# mMWCv0_2.net
KiCad netlist of a schematic drawn in EAGLE
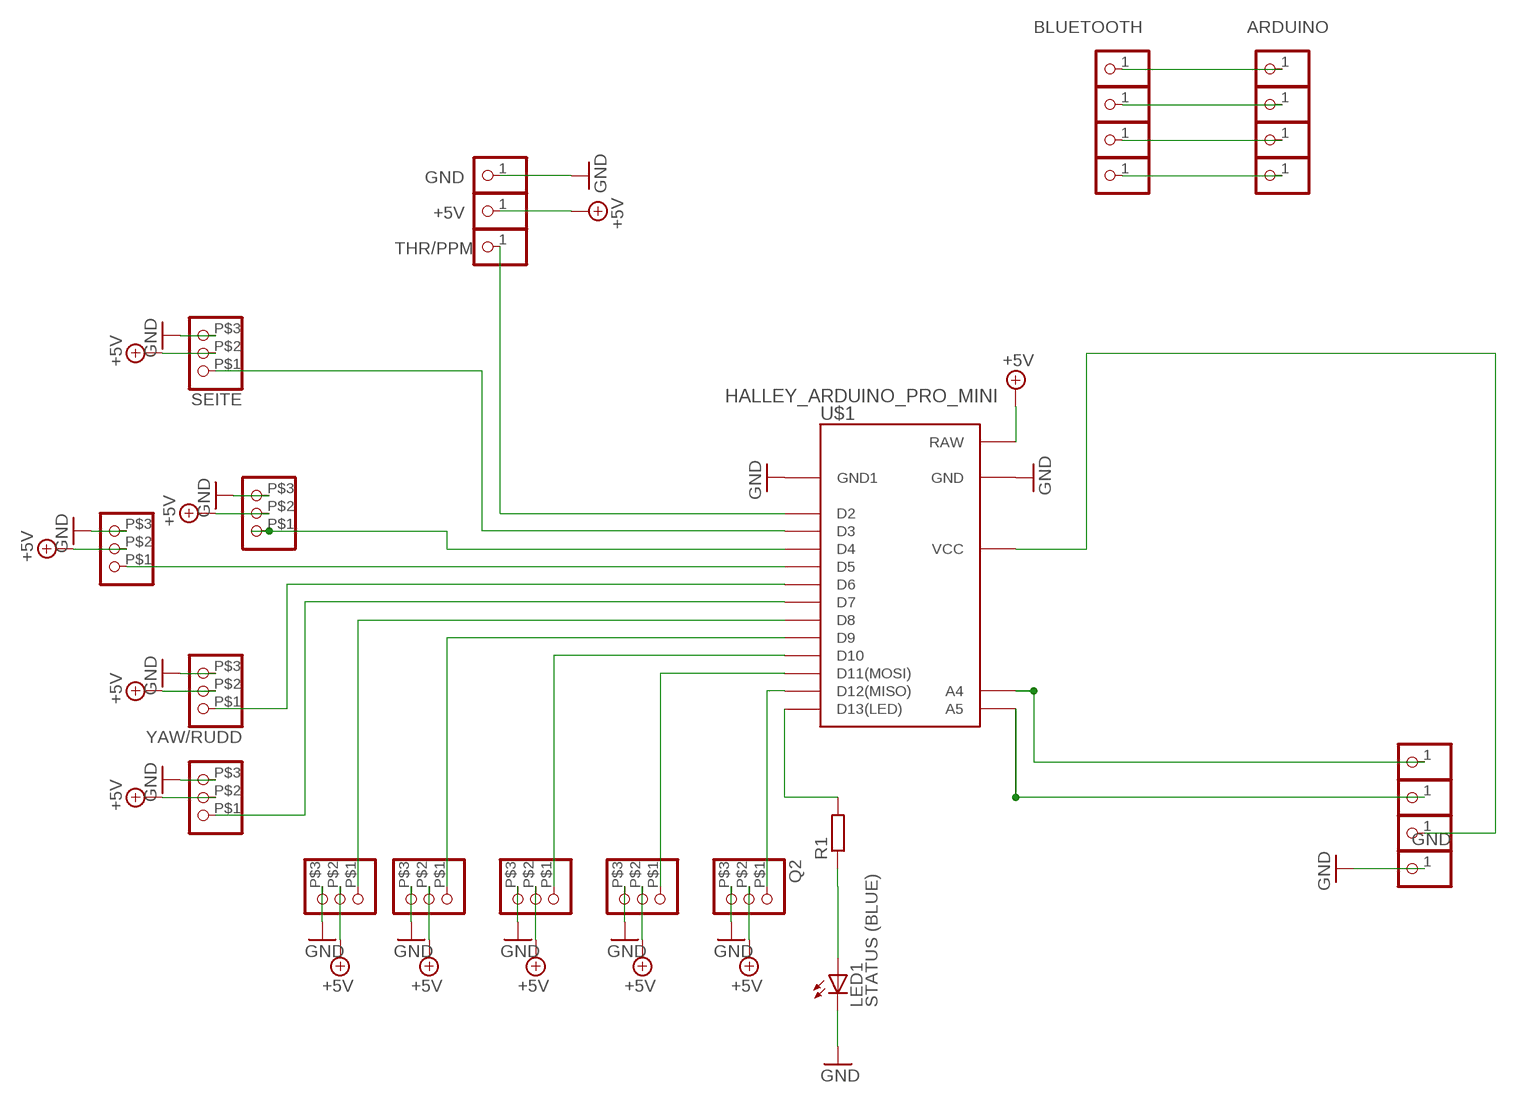
[diagram p0: schematic, sheet 1]

(export (version "E")
  (design (tool "Eeschema 10.0.6"))
  (components
    (comp (ref "+5V")
      (value "PINHD-1X1")
      (footprint "eagle-import:1X01")
      (libsource (lib "eagle-import") (part "PINHD-1X1"))
    )
    (comp (ref "5V")
      (value "PINHD-1X1")
      (footprint "eagle-import:1X01")
      (libsource (lib "eagle-import") (part "PINHD-1X1"))
    )
    (comp (ref "A4")
      (value "PINHD-1X1")
      (footprint "eagle-import:1X01")
      (libsource (lib "eagle-import") (part "PINHD-1X1"))
    )
    (comp (ref "A5")
      (value "PINHD-1X1")
      (footprint "eagle-import:1X01")
      (libsource (lib "eagle-import") (part "PINHD-1X1"))
    )
    (comp (ref "AIL")
      (value "PINHEAD_PINHD-1X3")
      (footprint "eagle-import:PINHEAD_1X03")
      (libsource (lib "eagle-import") (part "PINHEAD_PINHD-1X3"))
    )
    (comp (ref "ARD_GND")
      (value "PINHD-1X1")
      (footprint "eagle-import:1X01")
      (libsource (lib "eagle-import") (part "PINHD-1X1"))
    )
    (comp (ref "ARD_RX")
      (value "PINHD-1X1")
      (footprint "eagle-import:1X01")
      (libsource (lib "eagle-import") (part "PINHD-1X1"))
    )
    (comp (ref "ARD_TX")
      (value "PINHD-1X1")
      (footprint "eagle-import:1X01")
      (libsource (lib "eagle-import") (part "PINHD-1X1"))
    )
    (comp (ref "ARD_VCC")
      (value "GND")
      (footprint "eagle-import:1X01")
      (libsource (lib "eagle-import") (part "PINHD-1X1"))
    )
    (comp (ref "AUX2")
      (value "PINHEAD_PINHD-1X3")
      (footprint "eagle-import:PINHEAD_1X03")
      (libsource (lib "eagle-import") (part "PINHEAD_PINHD-1X3"))
    )
    (comp (ref "BT_GND")
      (value "PINHD-1X1")
      (footprint "eagle-import:1X01")
      (libsource (lib "eagle-import") (part "PINHD-1X1"))
    )
    (comp (ref "BT_RX")
      (value "PINHD-1X1")
      (footprint "eagle-import:1X01")
      (libsource (lib "eagle-import") (part "PINHD-1X1"))
    )
    (comp (ref "BT_TX")
      (value "PINHD-1X1")
      (footprint "eagle-import:1X01")
      (libsource (lib "eagle-import") (part "PINHD-1X1"))
    )
    (comp (ref "BT_VCC")
      (value "GND")
      (footprint "eagle-import:1X01")
      (libsource (lib "eagle-import") (part "PINHD-1X1"))
    )
    (comp (ref "ELE/PITCH")
      (value "PINHEAD_PINHD-1X3")
      (footprint "eagle-import:PINHEAD_1X03")
      (libsource (lib "eagle-import") (part "PINHEAD_PINHD-1X3"))
    )
    (comp (ref "GND")
      (value "PINHD-1X1")
      (footprint "eagle-import:1X01")
      (libsource (lib "eagle-import") (part "PINHD-1X1"))
    )
    (comp (ref "GND_")
      (value "GND")
      (footprint "eagle-import:1X01")
      (libsource (lib "eagle-import") (part "PINHD-1X1"))
    )
    (comp (ref "HÖHE")
      (value "PINHEAD_PINHD-1X3")
      (footprint "eagle-import:PINHEAD_1X03")
      (libsource (lib "eagle-import") (part "PINHEAD_PINHD-1X3"))
    )
    (comp (ref "LED1")
      (value "STATUS (BLUE)")
      (footprint "eagle-import:CHIPLED_1206")
      (libsource (lib "eagle-import") (part "LEDCHIPLED_1206"))
    )
    (comp (ref "MODE")
      (value "PINHEAD_PINHD-1X3")
      (footprint "eagle-import:PINHEAD_1X03")
      (libsource (lib "eagle-import") (part "PINHEAD_PINHD-1X3"))
    )
    (comp (ref "MOTOR")
      (value "PINHEAD_PINHD-1X3")
      (footprint "eagle-import:PINHEAD_1X03")
      (libsource (lib "eagle-import") (part "PINHEAD_PINHD-1X3"))
    )
    (comp (ref "Q1")
      (value "PINHEAD_PINHD-1X3")
      (footprint "eagle-import:PINHEAD_1X03")
      (libsource (lib "eagle-import") (part "PINHEAD_PINHD-1X3"))
    )
    (comp (ref "Q2")
      (value "PINHEAD_PINHD-1X3")
      (footprint "eagle-import:PINHEAD_1X03")
      (libsource (lib "eagle-import") (part "PINHEAD_PINHD-1X3"))
    )
    (comp (ref "R1")
      (value "R-EU_R1206")
      (footprint "eagle-import:R1206")
      (libsource (lib "eagle-import") (part "R-EU_R1206"))
    )
    (comp (ref "SEITE")
      (value "PINHEAD_PINHD-1X3")
      (footprint "eagle-import:PINHEAD_1X03")
      (libsource (lib "eagle-import") (part "PINHEAD_PINHD-1X3"))
    )
    (comp (ref "THR/PPM")
      (value "PINHD-1X1")
      (footprint "eagle-import:1X01")
      (libsource (lib "eagle-import") (part "PINHD-1X1"))
    )
    (comp (ref "U$1")
      (value "HALLEY_ARDUINO_PRO_MINI")
      (footprint "eagle-import:HALLEY_ARDUINO_PRO_MINI")
      (libsource (lib "eagle-import") (part "HALLEY_ARDUINO_PRO_MINI"))
    )
    (comp (ref "YAW/RUDD")
      (value "PINHEAD_PINHD-1X3")
      (footprint "eagle-import:PINHEAD_1X03")
      (libsource (lib "eagle-import") (part "PINHEAD_PINHD-1X3"))
    )
  )
  (nets
    (net (code "1") (name "+5V") (class "Default")
      (node (ref "+5V") (pin "1") (pinfunction "1_1") (pintype "passive"))
      (node (ref "AIL") (pin "P$2") (pinfunction "2_P$2") (pintype "passive"))
      (node (ref "AUX2") (pin "P$2") (pinfunction "2_P$2") (pintype "passive"))
      (node (ref "ELE/PITCH") (pin "P$2") (pinfunction "2_P$2") (pintype "passive"))
      (node (ref "HÖHE") (pin "P$2") (pinfunction "2_P$2") (pintype "passive"))
      (node (ref "MODE") (pin "P$2") (pinfunction "2_P$2") (pintype "passive"))
      (node (ref "MOTOR") (pin "P$2") (pinfunction "2_P$2") (pintype "passive"))
      (node (ref "Q1") (pin "P$2") (pinfunction "2_P$2") (pintype "passive"))
      (node (ref "Q2") (pin "P$2") (pinfunction "2_P$2") (pintype "passive"))
      (node (ref "SEITE") (pin "P$2") (pinfunction "2_P$2") (pintype "passive"))
      (node (ref "U$1") (pin "RAW") (pinfunction "RAW_RAW") (pintype "bidirectional"))
      (node (ref "YAW/RUDD") (pin "P$2") (pinfunction "2_P$2") (pintype "passive"))
    )
    (net (code "2") (name "GND") (class "Default")
      (node (ref "AIL") (pin "P$3") (pinfunction "3_P$3") (pintype "passive"))
      (node (ref "AUX2") (pin "P$3") (pinfunction "3_P$3") (pintype "passive"))
      (node (ref "ELE/PITCH") (pin "P$3") (pinfunction "3_P$3") (pintype "passive"))
      (node (ref "GND") (pin "1") (pinfunction "1_1") (pintype "passive"))
      (node (ref "GND_") (pin "1") (pinfunction "1_1") (pintype "passive"))
      (node (ref "HÖHE") (pin "P$3") (pinfunction "3_P$3") (pintype "passive"))
      (node (ref "LED1") (pin "C") (pinfunction "C_C") (pintype "passive"))
      (node (ref "MODE") (pin "P$3") (pinfunction "3_P$3") (pintype "passive"))
      (node (ref "MOTOR") (pin "P$3") (pinfunction "3_P$3") (pintype "passive"))
      (node (ref "Q1") (pin "P$3") (pinfunction "3_P$3") (pintype "passive"))
      (node (ref "Q2") (pin "P$3") (pinfunction "3_P$3") (pintype "passive"))
      (node (ref "SEITE") (pin "P$3") (pinfunction "3_P$3") (pintype "passive"))
      (node (ref "U$1") (pin "GND") (pinfunction "GND1_GND") (pintype "bidirectional"))
      (node (ref "U$1") (pin "GND1") (pinfunction "GND_GND1") (pintype "bidirectional"))
      (node (ref "YAW/RUDD") (pin "P$3") (pinfunction "3_P$3") (pintype "passive"))
    )
    (net (code "3") (name "Net-(5V-Pad1)") (class "Default")
      (node (ref "5V") (pin "1") (pinfunction "1_1") (pintype "passive"))
      (node (ref "U$1") (pin "VCC") (pinfunction "VCC_VCC") (pintype "bidirectional"))
    )
    (net (code "4") (name "Net-(A4-Pad1)") (class "Default")
      (node (ref "A4") (pin "1") (pinfunction "1_1") (pintype "passive"))
      (node (ref "U$1") (pin "A4") (pinfunction "A4_A4") (pintype "bidirectional"))
    )
    (net (code "5") (name "Net-(A5-Pad1)") (class "Default")
      (node (ref "A5") (pin "1") (pinfunction "1_1") (pintype "passive"))
      (node (ref "U$1") (pin "A5") (pinfunction "A5_A5") (pintype "bidirectional"))
    )
    (net (code "6") (name "Net-(AIL-1)") (class "Default")
      (node (ref "AIL") (pin "P$1") (pinfunction "1_P$1") (pintype "passive"))
      (node (ref "U$1") (pin "D4") (pinfunction "D4_D4") (pintype "bidirectional"))
    )
    (net (code "7") (name "Net-(ARD_GND-Pad1)") (class "Default")
      (node (ref "ARD_GND") (pin "1") (pinfunction "1_1") (pintype "passive"))
      (node (ref "BT_GND") (pin "1") (pinfunction "1_1") (pintype "passive"))
    )
    (net (code "8") (name "Net-(ARD_RX-Pad1)") (class "Default")
      (node (ref "ARD_RX") (pin "1") (pinfunction "1_1") (pintype "passive"))
      (node (ref "BT_TX") (pin "1") (pinfunction "1_1") (pintype "passive"))
    )
    (net (code "9") (name "Net-(ARD_TX-Pad1)") (class "Default")
      (node (ref "ARD_TX") (pin "1") (pinfunction "1_1") (pintype "passive"))
      (node (ref "BT_RX") (pin "1") (pinfunction "1_1") (pintype "passive"))
    )
    (net (code "10") (name "Net-(ARD_VCC-Pad1)") (class "Default")
      (node (ref "ARD_VCC") (pin "1") (pinfunction "1_1") (pintype "passive"))
      (node (ref "BT_VCC") (pin "1") (pinfunction "1_1") (pintype "passive"))
    )
    (net (code "11") (name "Net-(AUX2-1)") (class "Default")
      (node (ref "AUX2") (pin "P$1") (pinfunction "1_P$1") (pintype "passive"))
      (node (ref "U$1") (pin "D8") (pinfunction "D8_D8") (pintype "bidirectional"))
    )
    (net (code "12") (name "Net-(ELE/PITCH-1)") (class "Default")
      (node (ref "ELE/PITCH") (pin "P$1") (pinfunction "1_P$1") (pintype "passive"))
      (node (ref "U$1") (pin "D5") (pinfunction "D5_D5") (pintype "bidirectional"))
    )
    (net (code "13") (name "Net-(HÖHE-1)") (class "Default")
      (node (ref "HÖHE") (pin "P$1") (pinfunction "1_P$1") (pintype "passive"))
      (node (ref "U$1") (pin "D10") (pinfunction "D10_D10") (pintype "bidirectional"))
    )
    (net (code "14") (name "Net-(LED1-PadA)") (class "Default")
      (node (ref "LED1") (pin "A") (pinfunction "A_A") (pintype "passive"))
      (node (ref "R1") (pin "1") (pinfunction "1_1") (pintype "passive"))
    )
    (net (code "15") (name "Net-(MODE-1)") (class "Default")
      (node (ref "MODE") (pin "P$1") (pinfunction "1_P$1") (pintype "passive"))
      (node (ref "U$1") (pin "D7") (pinfunction "D7_D7") (pintype "bidirectional"))
    )
    (net (code "16") (name "Net-(MOTOR-1)") (class "Default")
      (node (ref "MOTOR") (pin "P$1") (pinfunction "1_P$1") (pintype "passive"))
      (node (ref "U$1") (pin "D9") (pinfunction "D9_D9") (pintype "bidirectional"))
    )
    (net (code "17") (name "Net-(Q1-1)") (class "Default")
      (node (ref "Q1") (pin "P$1") (pinfunction "1_P$1") (pintype "passive"))
      (node (ref "U$1") (pin "D11") (pinfunction "D11(MOSI)_D11") (pintype "bidirectional"))
    )
    (net (code "18") (name "Net-(Q2-1)") (class "Default")
      (node (ref "Q2") (pin "P$1") (pinfunction "1_P$1") (pintype "passive"))
      (node (ref "U$1") (pin "D12") (pinfunction "D12(MISO)_D12") (pintype "bidirectional"))
    )
    (net (code "19") (name "Net-(SEITE-1)") (class "Default")
      (node (ref "SEITE") (pin "P$1") (pinfunction "1_P$1") (pintype "passive"))
      (node (ref "U$1") (pin "D3") (pinfunction "D3_D3") (pintype "bidirectional"))
    )
    (net (code "20") (name "Net-(THR/PPM-Pad1)") (class "Default")
      (node (ref "THR/PPM") (pin "1") (pinfunction "1_1") (pintype "passive"))
      (node (ref "U$1") (pin "D2") (pinfunction "D2_D2") (pintype "bidirectional"))
    )
    (net (code "21") (name "Net-(U$1-D13(LED))") (class "Default")
      (node (ref "R1") (pin "2") (pinfunction "2_2") (pintype "passive"))
      (node (ref "U$1") (pin "D13") (pinfunction "D13(LED)_D13") (pintype "bidirectional"))
    )
    (net (code "22") (name "Net-(YAW/RUDD-1)") (class "Default")
      (node (ref "U$1") (pin "D6") (pinfunction "D6_D6") (pintype "bidirectional"))
      (node (ref "YAW/RUDD") (pin "P$1") (pinfunction "1_P$1") (pintype "passive"))
    )
  )
)
